# output_gains.net
KiCad netlist of a schematic drawn in Altium Designer
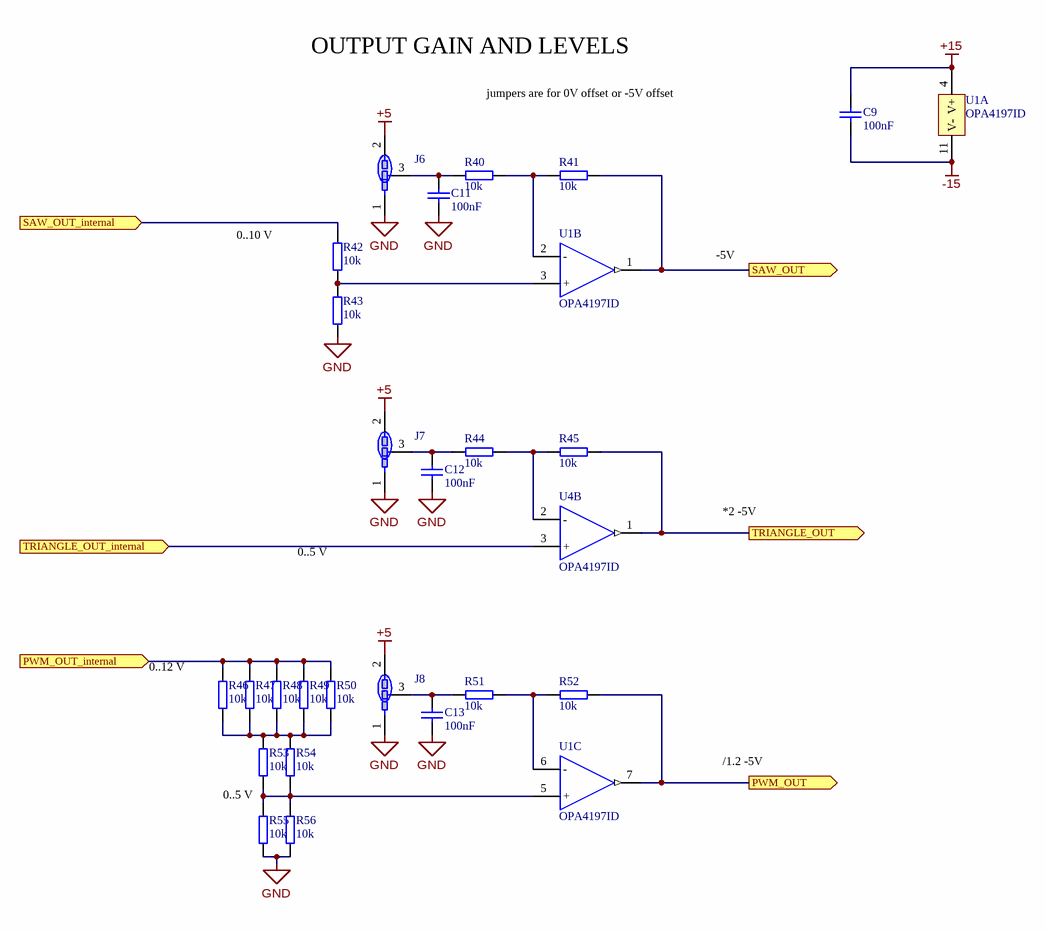
[diagram p0: output_gains.SchDoc]

(export (version "E")
  (design (tool "Eeschema 10.0.6"))
  (components
    (comp (ref "C9")
      (value "100nF")
      (footprint "WCAP-CSGP_0603_L1.6W0.8H0.8_Reflow")
      (description "WCAP-CSGP Multilayer Ceramic Chip Capacitor, General Purpose, size 0603, X7R, 100nF, 50V")
      (fields
        (field (name "MANUFACTURER") "Wurth Elektronik")
        (field (name "MANUFACTURER PART NUMBER") "885012206095")
      )
      (libsource (lib "Altium_WCAP-CSGP (rev22a)") (part "885012206095"))
    )
    (comp (ref "C11")
      (value "100nF")
      (footprint "WCAP-CSGP_0603_L1.6W0.8H0.8_Reflow")
      (description "WCAP-CSGP Multilayer Ceramic Chip Capacitor, General Purpose, size 0603, X7R, 100nF, 50V")
      (fields
        (field (name "MANUFACTURER") "Wurth Elektronik")
        (field (name "MANUFACTURER PART NUMBER") "885012206095")
      )
      (libsource (lib "Altium_WCAP-CSGP (rev22a)") (part "885012206095"))
    )
    (comp (ref "C12")
      (value "100nF")
      (footprint "WCAP-CSGP_0603_L1.6W0.8H0.8_Reflow")
      (description "WCAP-CSGP Multilayer Ceramic Chip Capacitor, General Purpose, size 0603, X7R, 100nF, 50V")
      (fields
        (field (name "MANUFACTURER") "Wurth Elektronik")
        (field (name "MANUFACTURER PART NUMBER") "885012206095")
      )
      (libsource (lib "Altium_WCAP-CSGP (rev22a)") (part "885012206095"))
    )
    (comp (ref "C13")
      (value "100nF")
      (footprint "WCAP-CSGP_0603_L1.6W0.8H0.8_Reflow")
      (description "WCAP-CSGP Multilayer Ceramic Chip Capacitor, General Purpose, size 0603, X7R, 100nF, 50V")
      (fields
        (field (name "MANUFACTURER") "Wurth Elektronik")
        (field (name "MANUFACTURER PART NUMBER") "885012206095")
      )
      (libsource (lib "Altium_WCAP-CSGP (rev22a)") (part "885012206095"))
    )
    (comp (ref "J6")
      (value "~")
      (footprint "JUMPER3_SMT_1LAYER")
      (description "De; Soldering Jumper;")
      (libsource (lib "altium_sql") (part "JUMPER_3P"))
    )
    (comp (ref "J7")
      (value "~")
      (footprint "JUMPER3_SMT_1LAYER")
      (description "De; Soldering Jumper;")
      (libsource (lib "altium_sql") (part "JUMPER_3P"))
    )
    (comp (ref "J8")
      (value "~")
      (footprint "JUMPER3_SMT_1LAYER")
      (description "De; Soldering Jumper;")
      (libsource (lib "altium_sql") (part "JUMPER_3P"))
    )
    (comp (ref "R40")
      (value "10k")
      (footprint "RESC1608X06N(SMR0603)")
      (description "Thick Film resistor, 0603 Size, universal value, 0.1 W")
      (libsource (lib "Kubikova integrovana knihovna ") (part "R 0603 universal"))
    )
    (comp (ref "R41")
      (value "10k")
      (footprint "RESC1608X06N(SMR0603)")
      (description "Thick Film resistor, 0603 Size, universal value, 0.1 W")
      (libsource (lib "Kubikova integrovana knihovna ") (part "R 0603 universal"))
    )
    (comp (ref "R42")
      (value "10k")
      (footprint "RESC1608X06N(SMR0603)")
      (description "Thick Film resistor, 0603 Size, universal value, 0.1 W")
      (libsource (lib "Kubikova integrovana knihovna ") (part "R 0603 universal"))
    )
    (comp (ref "R43")
      (value "10k")
      (footprint "RESC1608X06N(SMR0603)")
      (description "Thick Film resistor, 0603 Size, universal value, 0.1 W")
      (libsource (lib "Kubikova integrovana knihovna ") (part "R 0603 universal"))
    )
    (comp (ref "R44")
      (value "10k")
      (footprint "RESC1608X06N(SMR0603)")
      (description "Thick Film resistor, 0603 Size, universal value, 0.1 W")
      (libsource (lib "Kubikova integrovana knihovna ") (part "R 0603 universal"))
    )
    (comp (ref "R45")
      (value "10k")
      (footprint "RESC1608X06N(SMR0603)")
      (description "Thick Film resistor, 0603 Size, universal value, 0.1 W")
      (libsource (lib "Kubikova integrovana knihovna ") (part "R 0603 universal"))
    )
    (comp (ref "R46")
      (value "10k")
      (footprint "RESC1608X06N(SMR0603)")
      (description "Thick Film resistor, 0603 Size, universal value, 0.1 W")
      (libsource (lib "Kubikova integrovana knihovna ") (part "R 0603 universal"))
    )
    (comp (ref "R47")
      (value "10k")
      (footprint "RESC1608X06N(SMR0603)")
      (description "Thick Film resistor, 0603 Size, universal value, 0.1 W")
      (libsource (lib "Kubikova integrovana knihovna ") (part "R 0603 universal"))
    )
    (comp (ref "R48")
      (value "10k")
      (footprint "RESC1608X06N(SMR0603)")
      (description "Thick Film resistor, 0603 Size, universal value, 0.1 W")
      (libsource (lib "Kubikova integrovana knihovna ") (part "R 0603 universal"))
    )
    (comp (ref "R49")
      (value "10k")
      (footprint "RESC1608X06N(SMR0603)")
      (description "Thick Film resistor, 0603 Size, universal value, 0.1 W")
      (libsource (lib "Kubikova integrovana knihovna ") (part "R 0603 universal"))
    )
    (comp (ref "R50")
      (value "10k")
      (footprint "RESC1608X06N(SMR0603)")
      (description "Thick Film resistor, 0603 Size, universal value, 0.1 W")
      (libsource (lib "Kubikova integrovana knihovna ") (part "R 0603 universal"))
    )
    (comp (ref "R51")
      (value "10k")
      (footprint "RESC1608X06N(SMR0603)")
      (description "Thick Film resistor, 0603 Size, universal value, 0.1 W")
      (libsource (lib "Kubikova integrovana knihovna ") (part "R 0603 universal"))
    )
    (comp (ref "R52")
      (value "10k")
      (footprint "RESC1608X06N(SMR0603)")
      (description "Thick Film resistor, 0603 Size, universal value, 0.1 W")
      (libsource (lib "Kubikova integrovana knihovna ") (part "R 0603 universal"))
    )
    (comp (ref "R53")
      (value "10k")
      (footprint "RESC1608X06N(SMR0603)")
      (description "Thick Film resistor, 0603 Size, universal value, 0.1 W")
      (libsource (lib "Kubikova integrovana knihovna ") (part "R 0603 universal"))
    )
    (comp (ref "R54")
      (value "10k")
      (footprint "RESC1608X06N(SMR0603)")
      (description "Thick Film resistor, 0603 Size, universal value, 0.1 W")
      (libsource (lib "Kubikova integrovana knihovna ") (part "R 0603 universal"))
    )
    (comp (ref "R55")
      (value "10k")
      (footprint "RESC1608X06N(SMR0603)")
      (description "Thick Film resistor, 0603 Size, universal value, 0.1 W")
      (libsource (lib "Kubikova integrovana knihovna ") (part "R 0603 universal"))
    )
    (comp (ref "R56")
      (value "10k")
      (footprint "RESC1608X06N(SMR0603)")
      (description "Thick Film resistor, 0603 Size, universal value, 0.1 W")
      (libsource (lib "Kubikova integrovana knihovna ") (part "R 0603 universal"))
    )
    (comp (ref "U1")
      (value "OPA4197ID")
      (footprint "SOIC127P600X175-14N(SO-14)")
      (description "IC; Opamp; 4.5V; 36V; 4x;")
      (libsource (lib "altium_sql") (part "OP_AMP_QUAD_1"))
    )
    (comp (ref "U4")
      (value "OPA4197ID")
      (footprint "SOIC127P600X175-14N(SO-14)")
      (description "IC; Opamp; 4.5V; 36V; 4x;")
      (libsource (lib "altium_sql") (part "OP_AMP_QUAD_1"))
    )
  )
  (nets
    (net (code "1") (name "+5") (class "Default")
      (node (ref "J6") (pin "2") (pinfunction "2_2") (pintype "passive"))
      (node (ref "J7") (pin "2") (pinfunction "2_2") (pintype "passive"))
      (node (ref "J8") (pin "2") (pinfunction "2_2") (pintype "passive"))
    )
    (net (code "2") (name "+15") (class "Default")
      (node (ref "C9") (pin "2") (pinfunction "2_2") (pintype "passive"))
      (node (ref "U1") (pin "4") (pinfunction "V+_4") (pintype "power_in"))
    )
    (net (code "3") (name "-15") (class "Default")
      (node (ref "C9") (pin "1") (pinfunction "1_1") (pintype "passive"))
      (node (ref "U1") (pin "11") (pinfunction "V-_11") (pintype "power_in"))
    )
    (net (code "4") (name "/PWM_OUT") (class "Default")
      (node (ref "R52") (pin "1") (pinfunction "1_1") (pintype "passive"))
      (node (ref "U1") (pin "7") (pinfunction "OUT2_7") (pintype "output"))
    )
    (net (code "5") (name "/PWM_OUT_internal") (class "Default")
      (node (ref "R46") (pin "1") (pinfunction "1_1") (pintype "passive"))
      (node (ref "R47") (pin "1") (pinfunction "1_1") (pintype "passive"))
      (node (ref "R48") (pin "1") (pinfunction "1_1") (pintype "passive"))
      (node (ref "R49") (pin "1") (pinfunction "1_1") (pintype "passive"))
      (node (ref "R50") (pin "1") (pinfunction "1_1") (pintype "passive"))
    )
    (net (code "6") (name "/SAW_OUT") (class "Default")
      (node (ref "R41") (pin "1") (pinfunction "1_1") (pintype "passive"))
      (node (ref "U1") (pin "1") (pinfunction "OUT1_1") (pintype "output"))
    )
    (net (code "7") (name "/SAW_OUT_internal") (class "Default")
      (node (ref "R42") (pin "2") (pinfunction "2_2") (pintype "passive"))
    )
    (net (code "8") (name "/TRIANGLE_OUT") (class "Default")
      (node (ref "R45") (pin "1") (pinfunction "1_1") (pintype "passive"))
      (node (ref "U4") (pin "1") (pinfunction "OUT1_1") (pintype "output"))
    )
    (net (code "9") (name "/TRIANGLE_OUT_internal") (class "Default")
      (node (ref "U4") (pin "3") (pinfunction "+_3") (pintype "passive"))
    )
    (net (code "10") (name "GND") (class "Default")
      (node (ref "C11") (pin "1") (pinfunction "1_1") (pintype "passive"))
      (node (ref "C12") (pin "1") (pinfunction "1_1") (pintype "passive"))
      (node (ref "C13") (pin "1") (pinfunction "1_1") (pintype "passive"))
      (node (ref "J6") (pin "1") (pinfunction "1_1") (pintype "passive"))
      (node (ref "J7") (pin "1") (pinfunction "1_1") (pintype "passive"))
      (node (ref "J8") (pin "1") (pinfunction "1_1") (pintype "passive"))
      (node (ref "R43") (pin "1") (pinfunction "1_1") (pintype "passive"))
      (node (ref "R55") (pin "2") (pinfunction "2_2") (pintype "passive"))
      (node (ref "R56") (pin "2") (pinfunction "2_2") (pintype "passive"))
    )
    (net (code "11") (name "Net-(C11-Pad2)") (class "Default")
      (node (ref "C11") (pin "2") (pinfunction "2_2") (pintype "passive"))
      (node (ref "J6") (pin "3") (pinfunction "3_3") (pintype "passive"))
      (node (ref "R40") (pin "2") (pinfunction "2_2") (pintype "passive"))
    )
    (net (code "12") (name "Net-(C12-Pad2)") (class "Default")
      (node (ref "C12") (pin "2") (pinfunction "2_2") (pintype "passive"))
      (node (ref "J7") (pin "3") (pinfunction "3_3") (pintype "passive"))
      (node (ref "R44") (pin "2") (pinfunction "2_2") (pintype "passive"))
    )
    (net (code "13") (name "Net-(C13-Pad2)") (class "Default")
      (node (ref "C13") (pin "2") (pinfunction "2_2") (pintype "passive"))
      (node (ref "J8") (pin "3") (pinfunction "3_3") (pintype "passive"))
      (node (ref "R51") (pin "2") (pinfunction "2_2") (pintype "passive"))
    )
    (net (code "14") (name "Net-(R46-Pad2)") (class "Default")
      (node (ref "R46") (pin "2") (pinfunction "2_2") (pintype "passive"))
      (node (ref "R47") (pin "2") (pinfunction "2_2") (pintype "passive"))
      (node (ref "R48") (pin "2") (pinfunction "2_2") (pintype "passive"))
      (node (ref "R49") (pin "2") (pinfunction "2_2") (pintype "passive"))
      (node (ref "R50") (pin "2") (pinfunction "2_2") (pintype "passive"))
      (node (ref "R53") (pin "1") (pinfunction "1_1") (pintype "passive"))
      (node (ref "R54") (pin "1") (pinfunction "1_1") (pintype "passive"))
    )
    (net (code "15") (name "Net-(U1B-+)") (class "Default")
      (node (ref "R42") (pin "1") (pinfunction "1_1") (pintype "passive"))
      (node (ref "R43") (pin "2") (pinfunction "2_2") (pintype "passive"))
      (node (ref "U1") (pin "3") (pinfunction "+_3") (pintype "passive"))
    )
    (net (code "16") (name "Net-(U1B--)") (class "Default")
      (node (ref "R40") (pin "1") (pinfunction "1_1") (pintype "passive"))
      (node (ref "R41") (pin "2") (pinfunction "2_2") (pintype "passive"))
      (node (ref "U1") (pin "2") (pinfunction "-_2") (pintype "passive"))
    )
    (net (code "17") (name "Net-(U1C-+)") (class "Default")
      (node (ref "R53") (pin "2") (pinfunction "2_2") (pintype "passive"))
      (node (ref "R54") (pin "2") (pinfunction "2_2") (pintype "passive"))
      (node (ref "R55") (pin "1") (pinfunction "1_1") (pintype "passive"))
      (node (ref "R56") (pin "1") (pinfunction "1_1") (pintype "passive"))
      (node (ref "U1") (pin "5") (pinfunction "+_5") (pintype "passive"))
    )
    (net (code "18") (name "Net-(U1C--)") (class "Default")
      (node (ref "R51") (pin "1") (pinfunction "1_1") (pintype "passive"))
      (node (ref "R52") (pin "2") (pinfunction "2_2") (pintype "passive"))
      (node (ref "U1") (pin "6") (pinfunction "-_6") (pintype "passive"))
    )
    (net (code "19") (name "Net-(U4B--)") (class "Default")
      (node (ref "R44") (pin "1") (pinfunction "1_1") (pintype "passive"))
      (node (ref "R45") (pin "2") (pinfunction "2_2") (pintype "passive"))
      (node (ref "U4") (pin "2") (pinfunction "-_2") (pintype "passive"))
    )
  )
)
